# RFMC_DAC.net
KiCad netlist of a schematic drawn in Altium Designer
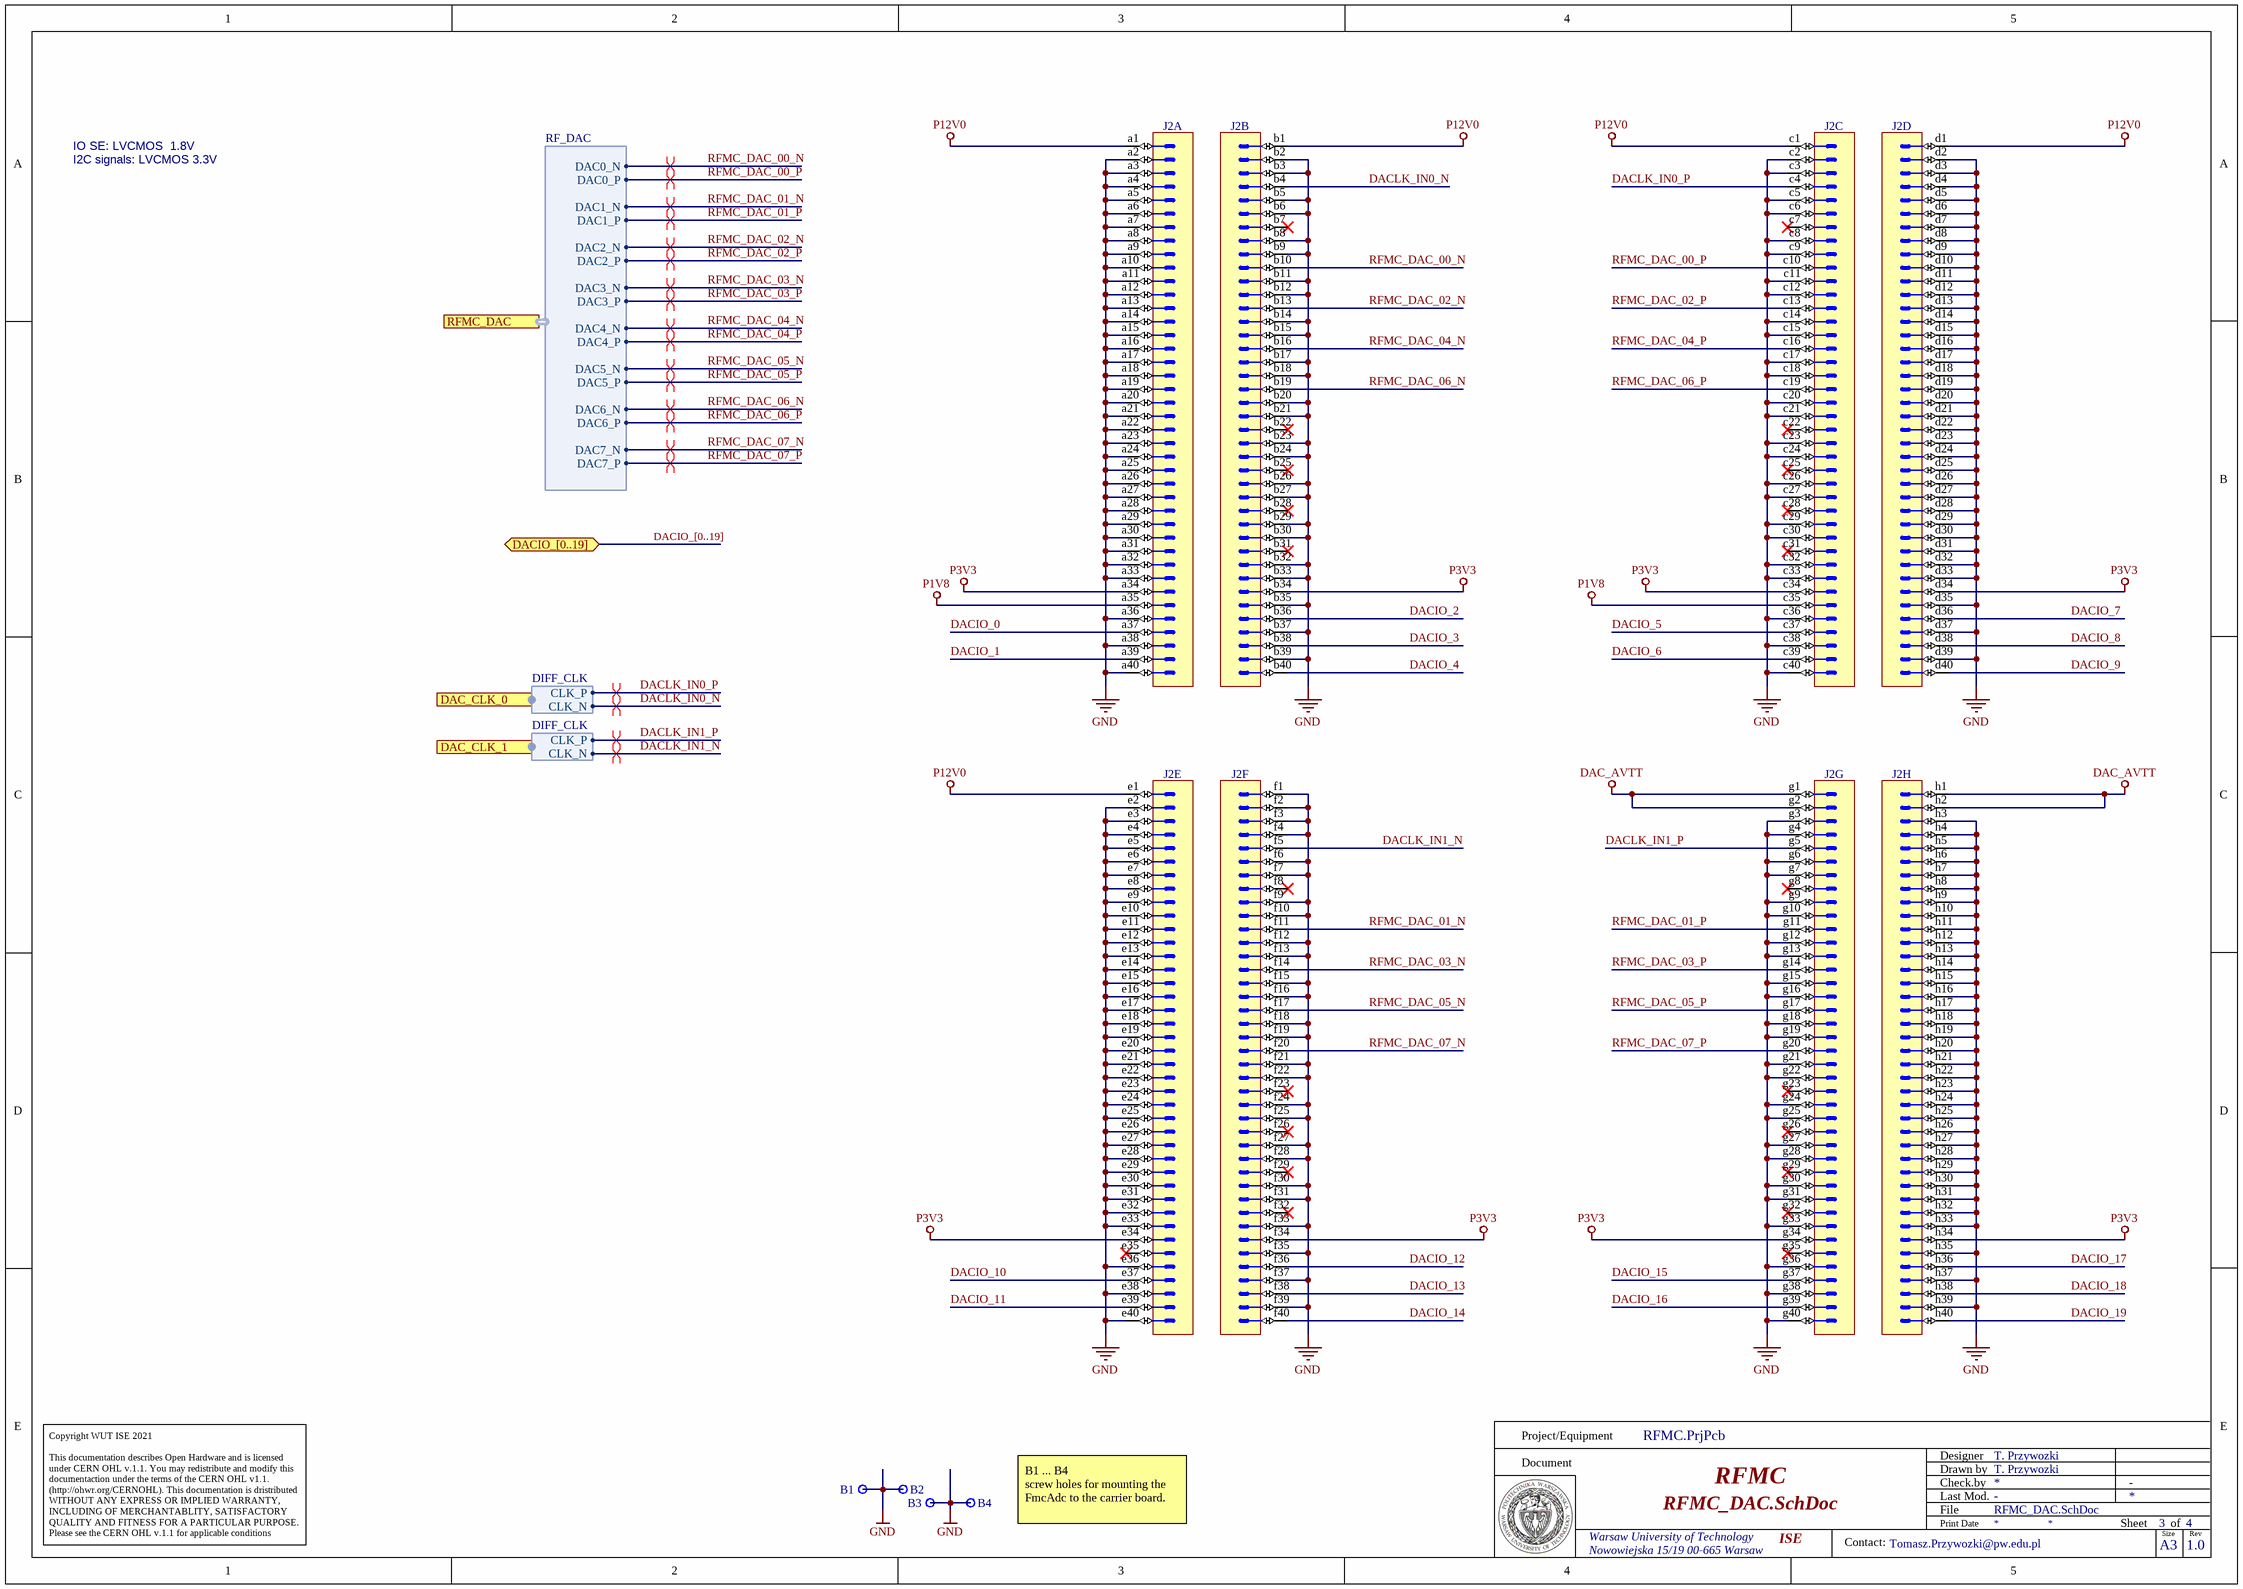
[diagram p0: RFMC_DAC.SchDoc]

(export (version "E")
  (design (tool "Eeschema 10.0.6"))
  (components
    (comp (ref "B1")
      (value "Plated Hole")
      (footprint "MTG270_500")
      (description "Single Terminal Socket")
      (fields (field (name "PART NUMBER") "PLATED_HOLE2.7_PAD5.0") (field (name "AUTHOR") "CERN DEM JMW"))
      (libsource (lib "Eletro-mechanical") (part "Single Terminal Socket"))
    )
    (comp (ref "B2")
      (value "Plated Hole")
      (footprint "MTG270_500")
      (description "Single Terminal Socket")
      (fields (field (name "PART NUMBER") "PLATED_HOLE2.7_PAD5.0") (field (name "AUTHOR") "CERN DEM JMW"))
      (libsource (lib "Eletro-mechanical") (part "Single Terminal Socket"))
    )
    (comp (ref "B3")
      (value "Plated Hole")
      (footprint "MTG270_500")
      (description "Single Terminal Socket")
      (fields (field (name "PART NUMBER") "PLATED_HOLE2.7_PAD5.0") (field (name "AUTHOR") "CERN DEM JMW"))
      (libsource (lib "Eletro-mechanical") (part "Single Terminal Socket"))
    )
    (comp (ref "B4")
      (value "Plated Hole")
      (footprint "MTG270_500")
      (description "Single Terminal Socket")
      (fields (field (name "PART NUMBER") "PLATED_HOLE2.7_PAD5.0") (field (name "AUTHOR") "CERN DEM JMW"))
      (libsource (lib "Eletro-mechanical") (part "Single Terminal Socket"))
    )
    (comp (ref "J2")
      (value "~")
      (footprint "SAMTEC_LPAM-40-01.0-S-08")
      (description "Connector 320 Male contacts in 8 row abcdef")
      (fields
        (field (name "PART NUMBER") "SAMTEC_LPAM-40-01.0-S-08-2-K")
        (field (name "MANUFACTURER") "SAMTEC")
        (field (name "AUTHOR") "CERN DEM BC")
      )
      (libsource (lib "Connectors") (part "Connector 320 Male (8x40) (abcdefgh)"))
    )
  )
  (nets
    (net (code "3") (name "/DACIO_0") (class "Default")
      (node (ref "J2") (pin "a37") (pinfunction "a37_a37") (pintype "bidirectional"))
    )
    (net (code "4") (name "/DACIO_1") (class "Default")
      (node (ref "J2") (pin "a39") (pinfunction "a39_a39") (pintype "bidirectional"))
    )
    (net (code "5") (name "/DACIO_2") (class "Default")
      (node (ref "J2") (pin "b36") (pinfunction "b36_b36") (pintype "bidirectional"))
    )
    (net (code "6") (name "/DACIO_3") (class "Default")
      (node (ref "J2") (pin "b38") (pinfunction "b38_b38") (pintype "bidirectional"))
    )
    (net (code "7") (name "/DACIO_4") (class "Default")
      (node (ref "J2") (pin "b40") (pinfunction "b40_b40") (pintype "bidirectional"))
    )
    (net (code "8") (name "/DACIO_5") (class "Default")
      (node (ref "J2") (pin "c37") (pinfunction "c37_c37") (pintype "bidirectional"))
    )
    (net (code "9") (name "/DACIO_6") (class "Default")
      (node (ref "J2") (pin "c39") (pinfunction "c39_c39") (pintype "bidirectional"))
    )
    (net (code "10") (name "/DACIO_7") (class "Default")
      (node (ref "J2") (pin "d36") (pinfunction "d36_d36") (pintype "bidirectional"))
    )
    (net (code "11") (name "/DACIO_8") (class "Default")
      (node (ref "J2") (pin "d38") (pinfunction "d38_d38") (pintype "bidirectional"))
    )
    (net (code "12") (name "/DACIO_9") (class "Default")
      (node (ref "J2") (pin "d40") (pinfunction "d40_d40") (pintype "bidirectional"))
    )
    (net (code "13") (name "/DACIO_10") (class "Default")
      (node (ref "J2") (pin "e37") (pinfunction "e37_e37") (pintype "bidirectional"))
    )
    (net (code "14") (name "/DACIO_11") (class "Default")
      (node (ref "J2") (pin "e39") (pinfunction "e39_e39") (pintype "bidirectional"))
    )
    (net (code "15") (name "/DACIO_12") (class "Default")
      (node (ref "J2") (pin "f36") (pinfunction "f36_f36") (pintype "bidirectional"))
    )
    (net (code "16") (name "/DACIO_13") (class "Default")
      (node (ref "J2") (pin "f38") (pinfunction "f38_f38") (pintype "bidirectional"))
    )
    (net (code "17") (name "/DACIO_14") (class "Default")
      (node (ref "J2") (pin "f40") (pinfunction "f40_f40") (pintype "bidirectional"))
    )
    (net (code "18") (name "/DACIO_15") (class "Default")
      (node (ref "J2") (pin "g37") (pinfunction "g37_g37") (pintype "bidirectional"))
    )
    (net (code "19") (name "/DACIO_16") (class "Default")
      (node (ref "J2") (pin "g39") (pinfunction "g39_g39") (pintype "bidirectional"))
    )
    (net (code "20") (name "/DACIO_17") (class "Default")
      (node (ref "J2") (pin "h36") (pinfunction "h36_h36") (pintype "bidirectional"))
    )
    (net (code "21") (name "/DACIO_18") (class "Default")
      (node (ref "J2") (pin "h38") (pinfunction "h38_h38") (pintype "bidirectional"))
    )
    (net (code "22") (name "/DACIO_19") (class "Default")
      (node (ref "J2") (pin "h40") (pinfunction "h40_h40") (pintype "bidirectional"))
    )
    (net (code "24") (name "/DACLK_IN0_N") (class "Default")
      (node (ref "J2") (pin "b4") (pinfunction "b4_b4") (pintype "bidirectional"))
    )
    (net (code "25") (name "/DACLK_IN0_P") (class "Default")
      (node (ref "J2") (pin "c4") (pinfunction "c4_c4") (pintype "bidirectional"))
    )
    (net (code "26") (name "/DACLK_IN1_N") (class "Default")
      (node (ref "J2") (pin "f5") (pinfunction "f5_f5") (pintype "bidirectional"))
    )
    (net (code "27") (name "/DACLK_IN1_P") (class "Default")
      (node (ref "J2") (pin "g5") (pinfunction "g5_g5") (pintype "bidirectional"))
    )
    (net (code "28") (name "/RFMC_DAC_00_N") (class "Default")
      (node (ref "J2") (pin "b10") (pinfunction "b10_b10") (pintype "bidirectional"))
    )
    (net (code "29") (name "/RFMC_DAC_00_P") (class "Default")
      (node (ref "J2") (pin "c10") (pinfunction "c10_c10") (pintype "bidirectional"))
    )
    (net (code "30") (name "/RFMC_DAC_01_N") (class "Default")
      (node (ref "J2") (pin "f11") (pinfunction "f11_f11") (pintype "bidirectional"))
    )
    (net (code "31") (name "/RFMC_DAC_01_P") (class "Default")
      (node (ref "J2") (pin "g11") (pinfunction "g11_g11") (pintype "bidirectional"))
    )
    (net (code "32") (name "/RFMC_DAC_02_N") (class "Default")
      (node (ref "J2") (pin "b13") (pinfunction "b13_b13") (pintype "bidirectional"))
    )
    (net (code "33") (name "/RFMC_DAC_02_P") (class "Default")
      (node (ref "J2") (pin "c13") (pinfunction "c13_c13") (pintype "bidirectional"))
    )
    (net (code "34") (name "/RFMC_DAC_03_N") (class "Default")
      (node (ref "J2") (pin "f14") (pinfunction "f14_f14") (pintype "bidirectional"))
    )
    (net (code "35") (name "/RFMC_DAC_03_P") (class "Default")
      (node (ref "J2") (pin "g14") (pinfunction "g14_g14") (pintype "bidirectional"))
    )
    (net (code "36") (name "/RFMC_DAC_04_N") (class "Default")
      (node (ref "J2") (pin "b16") (pinfunction "b16_b16") (pintype "bidirectional"))
    )
    (net (code "37") (name "/RFMC_DAC_04_P") (class "Default")
      (node (ref "J2") (pin "c16") (pinfunction "c16_c16") (pintype "bidirectional"))
    )
    (net (code "38") (name "/RFMC_DAC_05_N") (class "Default")
      (node (ref "J2") (pin "f17") (pinfunction "f17_f17") (pintype "bidirectional"))
    )
    (net (code "39") (name "/RFMC_DAC_05_P") (class "Default")
      (node (ref "J2") (pin "g17") (pinfunction "g17_g17") (pintype "bidirectional"))
    )
    (net (code "40") (name "/RFMC_DAC_06_N") (class "Default")
      (node (ref "J2") (pin "b19") (pinfunction "b19_b19") (pintype "bidirectional"))
    )
    (net (code "41") (name "/RFMC_DAC_06_P") (class "Default")
      (node (ref "J2") (pin "c19") (pinfunction "c19_c19") (pintype "bidirectional"))
    )
    (net (code "42") (name "/RFMC_DAC_07_N") (class "Default")
      (node (ref "J2") (pin "f20") (pinfunction "f20_f20") (pintype "bidirectional"))
    )
    (net (code "43") (name "/RFMC_DAC_07_P") (class "Default")
      (node (ref "J2") (pin "g20") (pinfunction "g20_g20") (pintype "bidirectional"))
    )
    (net (code "46") (name "DAC_AVTT") (class "Default")
      (node (ref "J2") (pin "g1") (pinfunction "g1_g1") (pintype "bidirectional"))
      (node (ref "J2") (pin "g2") (pinfunction "g2_g2") (pintype "bidirectional"))
      (node (ref "J2") (pin "h1") (pinfunction "h1_h1") (pintype "bidirectional"))
      (node (ref "J2") (pin "h2") (pinfunction "h2_h2") (pintype "bidirectional"))
    )
    (net (code "47") (name "GND") (class "Default")
      (node (ref "B1") (pin "1") (pinfunction "1_1") (pintype "bidirectional"))
      (node (ref "B2") (pin "1") (pinfunction "1_1") (pintype "bidirectional"))
      (node (ref "B3") (pin "1") (pinfunction "1_1") (pintype "bidirectional"))
      (node (ref "B4") (pin "1") (pinfunction "1_1") (pintype "bidirectional"))
      (node (ref "J2") (pin "a10") (pinfunction "a10_a10") (pintype "bidirectional"))
      (node (ref "J2") (pin "a11") (pinfunction "a11_a11") (pintype "bidirectional"))
      (node (ref "J2") (pin "a12") (pinfunction "a12_a12") (pintype "bidirectional"))
      (node (ref "J2") (pin "a13") (pinfunction "a13_a13") (pintype "bidirectional"))
      (node (ref "J2") (pin "a14") (pinfunction "a14_a14") (pintype "bidirectional"))
      (node (ref "J2") (pin "a15") (pinfunction "a15_a15") (pintype "bidirectional"))
      (node (ref "J2") (pin "a16") (pinfunction "a16_a16") (pintype "bidirectional"))
      (node (ref "J2") (pin "a17") (pinfunction "a17_a17") (pintype "bidirectional"))
      (node (ref "J2") (pin "a18") (pinfunction "a18_a18") (pintype "bidirectional"))
      (node (ref "J2") (pin "a19") (pinfunction "a19_a19") (pintype "bidirectional"))
      (node (ref "J2") (pin "a2") (pinfunction "a2_a2") (pintype "bidirectional"))
      (node (ref "J2") (pin "a20") (pinfunction "a20_a20") (pintype "bidirectional"))
      (node (ref "J2") (pin "a21") (pinfunction "a21_a21") (pintype "bidirectional"))
      (node (ref "J2") (pin "a22") (pinfunction "a22_a22") (pintype "bidirectional"))
      (node (ref "J2") (pin "a23") (pinfunction "a23_a23") (pintype "bidirectional"))
      (node (ref "J2") (pin "a24") (pinfunction "a24_a24") (pintype "bidirectional"))
      (node (ref "J2") (pin "a25") (pinfunction "a25_a25") (pintype "bidirectional"))
      (node (ref "J2") (pin "a26") (pinfunction "a26_a26") (pintype "bidirectional"))
      (node (ref "J2") (pin "a27") (pinfunction "a27_a27") (pintype "bidirectional"))
      (node (ref "J2") (pin "a28") (pinfunction "a28_a28") (pintype "bidirectional"))
      (node (ref "J2") (pin "a29") (pinfunction "a29_a29") (pintype "bidirectional"))
      (node (ref "J2") (pin "a3") (pinfunction "a3_a3") (pintype "bidirectional"))
      (node (ref "J2") (pin "a30") (pinfunction "a30_a30") (pintype "bidirectional"))
      (node (ref "J2") (pin "a31") (pinfunction "a31_a31") (pintype "bidirectional"))
      (node (ref "J2") (pin "a32") (pinfunction "a32_a32") (pintype "bidirectional"))
      (node (ref "J2") (pin "a33") (pinfunction "a33_a33") (pintype "bidirectional"))
      (node (ref "J2") (pin "a36") (pinfunction "a36_a36") (pintype "bidirectional"))
      (node (ref "J2") (pin "a38") (pinfunction "a38_a38") (pintype "bidirectional"))
      (node (ref "J2") (pin "a4") (pinfunction "a4_a4") (pintype "bidirectional"))
      (node (ref "J2") (pin "a40") (pinfunction "a40_a40") (pintype "bidirectional"))
      (node (ref "J2") (pin "a5") (pinfunction "a5_a5") (pintype "bidirectional"))
      (node (ref "J2") (pin "a6") (pinfunction "a6_a6") (pintype "bidirectional"))
      (node (ref "J2") (pin "a7") (pinfunction "a7_a7") (pintype "bidirectional"))
      (node (ref "J2") (pin "a8") (pinfunction "a8_a8") (pintype "bidirectional"))
      (node (ref "J2") (pin "a9") (pinfunction "a9_a9") (pintype "bidirectional"))
      (node (ref "J2") (pin "b11") (pinfunction "b11_b11") (pintype "bidirectional"))
      (node (ref "J2") (pin "b12") (pinfunction "b12_b12") (pintype "bidirectional"))
      (node (ref "J2") (pin "b14") (pinfunction "b14_b14") (pintype "bidirectional"))
      (node (ref "J2") (pin "b15") (pinfunction "b15_b15") (pintype "bidirectional"))
      (node (ref "J2") (pin "b17") (pinfunction "b17_b17") (pintype "bidirectional"))
      (node (ref "J2") (pin "b18") (pinfunction "b18_b18") (pintype "bidirectional"))
      (node (ref "J2") (pin "b2") (pinfunction "b2_b2") (pintype "bidirectional"))
      (node (ref "J2") (pin "b20") (pinfunction "b20_b20") (pintype "bidirectional"))
      (node (ref "J2") (pin "b21") (pinfunction "b21_b21") (pintype "bidirectional"))
      (node (ref "J2") (pin "b23") (pinfunction "b23_b23") (pintype "bidirectional"))
      (node (ref "J2") (pin "b24") (pinfunction "b24_b24") (pintype "bidirectional"))
      (node (ref "J2") (pin "b26") (pinfunction "b26_b26") (pintype "bidirectional"))
      (node (ref "J2") (pin "b27") (pinfunction "b27_b27") (pintype "bidirectional"))
      (node (ref "J2") (pin "b29") (pinfunction "b29_b29") (pintype "bidirectional"))
      (node (ref "J2") (pin "b3") (pinfunction "b3_b3") (pintype "bidirectional"))
      (node (ref "J2") (pin "b30") (pinfunction "b30_b30") (pintype "bidirectional"))
      (node (ref "J2") (pin "b32") (pinfunction "b32_b32") (pintype "bidirectional"))
      (node (ref "J2") (pin "b33") (pinfunction "b33_b33") (pintype "bidirectional"))
      (node (ref "J2") (pin "b35") (pinfunction "b35_b35") (pintype "bidirectional"))
      (node (ref "J2") (pin "b37") (pinfunction "b37_b37") (pintype "bidirectional"))
      (node (ref "J2") (pin "b39") (pinfunction "b39_b39") (pintype "bidirectional"))
      (node (ref "J2") (pin "b5") (pinfunction "b5_b5") (pintype "bidirectional"))
      (node (ref "J2") (pin "b6") (pinfunction "b6_b6") (pintype "bidirectional"))
      (node (ref "J2") (pin "b8") (pinfunction "b8_b8") (pintype "bidirectional"))
      (node (ref "J2") (pin "b9") (pinfunction "b9_b9") (pintype "bidirectional"))
      (node (ref "J2") (pin "c11") (pinfunction "c11_c11") (pintype "bidirectional"))
      (node (ref "J2") (pin "c12") (pinfunction "c12_c12") (pintype "bidirectional"))
      (node (ref "J2") (pin "c14") (pinfunction "c14_c14") (pintype "bidirectional"))
      (node (ref "J2") (pin "c15") (pinfunction "c15_c15") (pintype "bidirectional"))
      (node (ref "J2") (pin "c17") (pinfunction "c17_c17") (pintype "bidirectional"))
      (node (ref "J2") (pin "c18") (pinfunction "c18_c18") (pintype "bidirectional"))
      (node (ref "J2") (pin "c2") (pinfunction "c2_c2") (pintype "bidirectional"))
      (node (ref "J2") (pin "c20") (pinfunction "c20_c20") (pintype "bidirectional"))
      (node (ref "J2") (pin "c21") (pinfunction "c21_c21") (pintype "bidirectional"))
      (node (ref "J2") (pin "c23") (pinfunction "c23_c23") (pintype "bidirectional"))
      (node (ref "J2") (pin "c24") (pinfunction "c24_c24") (pintype "bidirectional"))
      (node (ref "J2") (pin "c26") (pinfunction "c26_c26") (pintype "bidirectional"))
      (node (ref "J2") (pin "c27") (pinfunction "c27_c27") (pintype "bidirectional"))
      (node (ref "J2") (pin "c29") (pinfunction "c29_c29") (pintype "bidirectional"))
      (node (ref "J2") (pin "c3") (pinfunction "c3_c3") (pintype "bidirectional"))
      (node (ref "J2") (pin "c30") (pinfunction "c30_c30") (pintype "bidirectional"))
      (node (ref "J2") (pin "c32") (pinfunction "c32_c32") (pintype "bidirectional"))
      (node (ref "J2") (pin "c33") (pinfunction "c33_c33") (pintype "bidirectional"))
      (node (ref "J2") (pin "c36") (pinfunction "c36_c36") (pintype "bidirectional"))
      (node (ref "J2") (pin "c38") (pinfunction "c38_c38") (pintype "bidirectional"))
      (node (ref "J2") (pin "c40") (pinfunction "c40_c40") (pintype "bidirectional"))
      (node (ref "J2") (pin "c5") (pinfunction "c5_c5") (pintype "bidirectional"))
      (node (ref "J2") (pin "c6") (pinfunction "c6_c6") (pintype "bidirectional"))
      (node (ref "J2") (pin "c8") (pinfunction "c8_c8") (pintype "bidirectional"))
      (node (ref "J2") (pin "c9") (pinfunction "c9_c9") (pintype "bidirectional"))
      (node (ref "J2") (pin "d10") (pinfunction "d10_d10") (pintype "bidirectional"))
      (node (ref "J2") (pin "d11") (pinfunction "d11_d11") (pintype "bidirectional"))
      (node (ref "J2") (pin "d12") (pinfunction "d12_d12") (pintype "bidirectional"))
      (node (ref "J2") (pin "d13") (pinfunction "d13_d13") (pintype "bidirectional"))
      (node (ref "J2") (pin "d14") (pinfunction "d14_d14") (pintype "bidirectional"))
      (node (ref "J2") (pin "d15") (pinfunction "d15_d15") (pintype "bidirectional"))
      (node (ref "J2") (pin "d16") (pinfunction "d16_d16") (pintype "bidirectional"))
      (node (ref "J2") (pin "d17") (pinfunction "d17_d17") (pintype "bidirectional"))
      (node (ref "J2") (pin "d18") (pinfunction "d18_d18") (pintype "bidirectional"))
      (node (ref "J2") (pin "d19") (pinfunction "d19_d19") (pintype "bidirectional"))
      (node (ref "J2") (pin "d2") (pinfunction "d2_d2") (pintype "bidirectional"))
      (node (ref "J2") (pin "d20") (pinfunction "d20_d20") (pintype "bidirectional"))
      (node (ref "J2") (pin "d21") (pinfunction "d21_d21") (pintype "bidirectional"))
      (node (ref "J2") (pin "d22") (pinfunction "d22_d22") (pintype "bidirectional"))
      (node (ref "J2") (pin "d23") (pinfunction "d23_d23") (pintype "bidirectional"))
      (node (ref "J2") (pin "d24") (pinfunction "d24_d24") (pintype "bidirectional"))
      (node (ref "J2") (pin "d25") (pinfunction "d25_d25") (pintype "bidirectional"))
      (node (ref "J2") (pin "d26") (pinfunction "d26_d26") (pintype "bidirectional"))
      (node (ref "J2") (pin "d27") (pinfunction "d27_d27") (pintype "bidirectional"))
      (node (ref "J2") (pin "d28") (pinfunction "d28_d28") (pintype "bidirectional"))
      (node (ref "J2") (pin "d29") (pinfunction "d29_d29") (pintype "bidirectional"))
      (node (ref "J2") (pin "d3") (pinfunction "d3_d3") (pintype "bidirectional"))
      (node (ref "J2") (pin "d30") (pinfunction "d30_d30") (pintype "bidirectional"))
      (node (ref "J2") (pin "d31") (pinfunction "d31_d31") (pintype "bidirectional"))
      (node (ref "J2") (pin "d32") (pinfunction "d32_d32") (pintype "bidirectional"))
      (node (ref "J2") (pin "d33") (pinfunction "d33_d33") (pintype "bidirectional"))
      (node (ref "J2") (pin "d35") (pinfunction "d35_d35") (pintype "bidirectional"))
      (node (ref "J2") (pin "d37") (pinfunction "d37_d37") (pintype "bidirectional"))
      (node (ref "J2") (pin "d39") (pinfunction "d39_d39") (pintype "bidirectional"))
      (node (ref "J2") (pin "d4") (pinfunction "d4_d4") (pintype "bidirectional"))
      (node (ref "J2") (pin "d5") (pinfunction "d5_d5") (pintype "bidirectional"))
      (node (ref "J2") (pin "d6") (pinfunction "d6_d6") (pintype "bidirectional"))
      (node (ref "J2") (pin "d7") (pinfunction "d7_d7") (pintype "bidirectional"))
      (node (ref "J2") (pin "d8") (pinfunction "d8_d8") (pintype "bidirectional"))
      (node (ref "J2") (pin "d9") (pinfunction "d9_d9") (pintype "bidirectional"))
      (node (ref "J2") (pin "e10") (pinfunction "e10_e10") (pintype "bidirectional"))
      (node (ref "J2") (pin "e11") (pinfunction "e11_e11") (pintype "bidirectional"))
      (node (ref "J2") (pin "e12") (pinfunction "e12_e12") (pintype "bidirectional"))
      (node (ref "J2") (pin "e13") (pinfunction "e13_e13") (pintype "bidirectional"))
      (node (ref "J2") (pin "e14") (pinfunction "e14_e14") (pintype "bidirectional"))
      (node (ref "J2") (pin "e15") (pinfunction "e15_e15") (pintype "bidirectional"))
      (node (ref "J2") (pin "e16") (pinfunction "e16_e16") (pintype "bidirectional"))
      (node (ref "J2") (pin "e17") (pinfunction "e17_e17") (pintype "bidirectional"))
      (node (ref "J2") (pin "e18") (pinfunction "e18_e18") (pintype "bidirectional"))
      (node (ref "J2") (pin "e19") (pinfunction "e19_e19") (pintype "bidirectional"))
      (node (ref "J2") (pin "e2") (pinfunction "e2_e2") (pintype "bidirectional"))
      (node (ref "J2") (pin "e20") (pinfunction "e20_e20") (pintype "bidirectional"))
      (node (ref "J2") (pin "e21") (pinfunction "e21_e21") (pintype "bidirectional"))
      (node (ref "J2") (pin "e22") (pinfunction "e22_e22") (pintype "bidirectional"))
      (node (ref "J2") (pin "e23") (pinfunction "e23_e23") (pintype "bidirectional"))
      (node (ref "J2") (pin "e24") (pinfunction "e24_e24") (pintype "bidirectional"))
      (node (ref "J2") (pin "e25") (pinfunction "e25_e25") (pintype "bidirectional"))
      (node (ref "J2") (pin "e26") (pinfunction "e26_e26") (pintype "bidirectional"))
      (node (ref "J2") (pin "e27") (pinfunction "e27_e27") (pintype "bidirectional"))
      (node (ref "J2") (pin "e28") (pinfunction "e28_e28") (pintype "bidirectional"))
      (node (ref "J2") (pin "e29") (pinfunction "e29_e29") (pintype "bidirectional"))
      (node (ref "J2") (pin "e3") (pinfunction "e3_e3") (pintype "bidirectional"))
      (node (ref "J2") (pin "e30") (pinfunction "e30_e30") (pintype "bidirectional"))
      (node (ref "J2") (pin "e31") (pinfunction "e31_e31") (pintype "bidirectional"))
      (node (ref "J2") (pin "e32") (pinfunction "e32_e32") (pintype "bidirectional"))
      (node (ref "J2") (pin "e33") (pinfunction "e33_e33") (pintype "bidirectional"))
      (node (ref "J2") (pin "e36") (pinfunction "e36_e36") (pintype "bidirectional"))
      (node (ref "J2") (pin "e38") (pinfunction "e38_e38") (pintype "bidirectional"))
      (node (ref "J2") (pin "e4") (pinfunction "e4_e4") (pintype "bidirectional"))
      (node (ref "J2") (pin "e40") (pinfunction "e40_e40") (pintype "bidirectional"))
      (node (ref "J2") (pin "e5") (pinfunction "e5_e5") (pintype "bidirectional"))
      (node (ref "J2") (pin "e6") (pinfunction "e6_e6") (pintype "bidirectional"))
      (node (ref "J2") (pin "e7") (pinfunction "e7_e7") (pintype "bidirectional"))
      (node (ref "J2") (pin "e8") (pinfunction "e8_e8") (pintype "bidirectional"))
      (node (ref "J2") (pin "e9") (pinfunction "e9_e9") (pintype "bidirectional"))
      (node (ref "J2") (pin "f1") (pinfunction "f1_f1") (pintype "bidirectional"))
      (node (ref "J2") (pin "f10") (pinfunction "f10_f10") (pintype "bidirectional"))
      (node (ref "J2") (pin "f12") (pinfunction "f12_f12") (pintype "bidirectional"))
      (node (ref "J2") (pin "f13") (pinfunction "f13_f13") (pintype "bidirectional"))
      (node (ref "J2") (pin "f15") (pinfunction "f15_f15") (pintype "bidirectional"))
      (node (ref "J2") (pin "f16") (pinfunction "f16_f16") (pintype "bidirectional"))
      (node (ref "J2") (pin "f18") (pinfunction "f18_f18") (pintype "bidirectional"))
      (node (ref "J2") (pin "f19") (pinfunction "f19_f19") (pintype "bidirectional"))
      (node (ref "J2") (pin "f2") (pinfunction "f2_f2") (pintype "bidirectional"))
      (node (ref "J2") (pin "f21") (pinfunction "f21_f21") (pintype "bidirectional"))
      (node (ref "J2") (pin "f22") (pinfunction "f22_f22") (pintype "bidirectional"))
      (node (ref "J2") (pin "f24") (pinfunction "f24_f24") (pintype "bidirectional"))
      (node (ref "J2") (pin "f25") (pinfunction "f25_f25") (pintype "bidirectional"))
      (node (ref "J2") (pin "f27") (pinfunction "f27_f27") (pintype "bidirectional"))
      (node (ref "J2") (pin "f28") (pinfunction "f28_f28") (pintype "bidirectional"))
      (node (ref "J2") (pin "f3") (pinfunction "f3_f3") (pintype "bidirectional"))
      (node (ref "J2") (pin "f30") (pinfunction "f30_f30") (pintype "bidirectional"))
      (node (ref "J2") (pin "f31") (pinfunction "f31_f31") (pintype "bidirectional"))
      (node (ref "J2") (pin "f33") (pinfunction "f33_f33") (pintype "bidirectional"))
      (node (ref "J2") (pin "f35") (pinfunction "f35_f35") (pintype "bidirectional"))
      (node (ref "J2") (pin "f37") (pinfunction "f37_f37") (pintype "bidirectional"))
      (node (ref "J2") (pin "f39") (pinfunction "f39_f39") (pintype "bidirectional"))
      (node (ref "J2") (pin "f4") (pinfunction "f4_f4") (pintype "bidirectional"))
      (node (ref "J2") (pin "f6") (pinfunction "f6_f6") (pintype "bidirectional"))
      (node (ref "J2") (pin "f7") (pinfunction "f7_f7") (pintype "bidirectional"))
      (node (ref "J2") (pin "f9") (pinfunction "f9_f9") (pintype "bidirectional"))
      (node (ref "J2") (pin "g10") (pinfunction "g10_g10") (pintype "bidirectional"))
      (node (ref "J2") (pin "g12") (pinfunction "g12_g12") (pintype "bidirectional"))
      (node (ref "J2") (pin "g13") (pinfunction "g13_g13") (pintype "bidirectional"))
      (node (ref "J2") (pin "g15") (pinfunction "g15_g15") (pintype "bidirectional"))
      (node (ref "J2") (pin "g16") (pinfunction "g16_g16") (pintype "bidirectional"))
      (node (ref "J2") (pin "g18") (pinfunction "g18_g18") (pintype "bidirectional"))
      (node (ref "J2") (pin "g19") (pinfunction "g19_g19") (pintype "bidirectional"))
      (node (ref "J2") (pin "g21") (pinfunction "g21_g21") (pintype "bidirectional"))
      (node (ref "J2") (pin "g22") (pinfunction "g22_g22") (pintype "bidirectional"))
      (node (ref "J2") (pin "g24") (pinfunction "g24_g24") (pintype "bidirectional"))
      (node (ref "J2") (pin "g25") (pinfunction "g25_g25") (pintype "bidirectional"))
      (node (ref "J2") (pin "g27") (pinfunction "g27_g27") (pintype "bidirectional"))
      (node (ref "J2") (pin "g28") (pinfunction "g28_g28") (pintype "bidirectional"))
      (node (ref "J2") (pin "g3") (pinfunction "g3_g3") (pintype "bidirectional"))
      (node (ref "J2") (pin "g30") (pinfunction "g30_g30") (pintype "bidirectional"))
      (node (ref "J2") (pin "g31") (pinfunction "g31_g31") (pintype "bidirectional"))
      (node (ref "J2") (pin "g33") (pinfunction "g33_g33") (pintype "bidirectional"))
      (node (ref "J2") (pin "g36") (pinfunction "g36_g36") (pintype "bidirectional"))
      (node (ref "J2") (pin "g38") (pinfunction "g38_g38") (pintype "bidirectional"))
      (node (ref "J2") (pin "g4") (pinfunction "g4_g4") (pintype "bidirectional"))
      (node (ref "J2") (pin "g40") (pinfunction "g40_g40") (pintype "bidirectional"))
      (node (ref "J2") (pin "g6") (pinfunction "g6_g6") (pintype "bidirectional"))
      (node (ref "J2") (pin "g7") (pinfunction "g7_g7") (pintype "bidirectional"))
      (node (ref "J2") (pin "g9") (pinfunction "g9_g9") (pintype "bidirectional"))
      (node (ref "J2") (pin "h10") (pinfunction "h10_h10") (pintype "bidirectional"))
      (node (ref "J2") (pin "h11") (pinfunction "h11_h11") (pintype "bidirectional"))
      (node (ref "J2") (pin "h12") (pinfunction "h12_h12") (pintype "bidirectional"))
      (node (ref "J2") (pin "h13") (pinfunction "h13_h13") (pintype "bidirectional"))
      (node (ref "J2") (pin "h14") (pinfunction "h14_h14") (pintype "bidirectional"))
      (node (ref "J2") (pin "h15") (pinfunction "h15_h15") (pintype "bidirectional"))
      (node (ref "J2") (pin "h16") (pinfunction "h16_h16") (pintype "bidirectional"))
      (node (ref "J2") (pin "h17") (pinfunction "h17_h17") (pintype "bidirectional"))
      (node (ref "J2") (pin "h18") (pinfunction "h18_h18") (pintype "bidirectional"))
      (node (ref "J2") (pin "h19") (pinfunction "h19_h19") (pintype "bidirectional"))
      (node (ref "J2") (pin "h20") (pinfunction "h20_h20") (pintype "bidirectional"))
      (node (ref "J2") (pin "h21") (pinfunction "h21_h21") (pintype "bidirectional"))
      (node (ref "J2") (pin "h22") (pinfunction "h22_h22") (pintype "bidirectional"))
      (node (ref "J2") (pin "h23") (pinfunction "h23_h23") (pintype "bidirectional"))
      (node (ref "J2") (pin "h24") (pinfunction "h24_h24") (pintype "bidirectional"))
      (node (ref "J2") (pin "h25") (pinfunction "h25_h25") (pintype "bidirectional"))
      (node (ref "J2") (pin "h26") (pinfunction "h26_h26") (pintype "bidirectional"))
      (node (ref "J2") (pin "h27") (pinfunction "h27_h27") (pintype "bidirectional"))
      (node (ref "J2") (pin "h28") (pinfunction "h28_h28") (pintype "bidirectional"))
      (node (ref "J2") (pin "h29") (pinfunction "h29_h29") (pintype "bidirectional"))
      (node (ref "J2") (pin "h3") (pinfunction "h3_h3") (pintype "bidirectional"))
      (node (ref "J2") (pin "h30") (pinfunction "h30_h30") (pintype "bidirectional"))
      (node (ref "J2") (pin "h31") (pinfunction "h31_h31") (pintype "bidirectional"))
      (node (ref "J2") (pin "h32") (pinfunction "h32_h32") (pintype "bidirectional"))
      (node (ref "J2") (pin "h33") (pinfunction "h33_h33") (pintype "bidirectional"))
      (node (ref "J2") (pin "h35") (pinfunction "h35_h35") (pintype "bidirectional"))
      (node (ref "J2") (pin "h37") (pinfunction "h37_h37") (pintype "bidirectional"))
      (node (ref "J2") (pin "h39") (pinfunction "h39_h39") (pintype "bidirectional"))
      (node (ref "J2") (pin "h4") (pinfunction "h4_h4") (pintype "bidirectional"))
      (node (ref "J2") (pin "h5") (pinfunction "h5_h5") (pintype "bidirectional"))
      (node (ref "J2") (pin "h6") (pinfunction "h6_h6") (pintype "bidirectional"))
      (node (ref "J2") (pin "h7") (pinfunction "h7_h7") (pintype "bidirectional"))
      (node (ref "J2") (pin "h8") (pinfunction "h8_h8") (pintype "bidirectional"))
      (node (ref "J2") (pin "h9") (pinfunction "h9_h9") (pintype "bidirectional"))
    )
    (net (code "48") (name "P1V8") (class "Default")
      (node (ref "J2") (pin "a35") (pinfunction "a35_a35") (pintype "bidirectional"))
      (node (ref "J2") (pin "c35") (pinfunction "c35_c35") (pintype "bidirectional"))
    )
    (net (code "49") (name "P3V3") (class "Default")
      (node (ref "J2") (pin "a34") (pinfunction "a34_a34") (pintype "bidirectional"))
      (node (ref "J2") (pin "b34") (pinfunction "b34_b34") (pintype "bidirectional"))
      (node (ref "J2") (pin "c34") (pinfunction "c34_c34") (pintype "bidirectional"))
      (node (ref "J2") (pin "d34") (pinfunction "d34_d34") (pintype "bidirectional"))
      (node (ref "J2") (pin "e34") (pinfunction "e34_e34") (pintype "bidirectional"))
      (node (ref "J2") (pin "f34") (pinfunction "f34_f34") (pintype "bidirectional"))
      (node (ref "J2") (pin "g34") (pinfunction "g34_g34") (pintype "bidirectional"))
      (node (ref "J2") (pin "h34") (pinfunction "h34_h34") (pintype "bidirectional"))
    )
    (net (code "50") (name "P12V0") (class "Default")
      (node (ref "J2") (pin "a1") (pinfunction "a1_a1") (pintype "bidirectional"))
      (node (ref "J2") (pin "b1") (pinfunction "b1_b1") (pintype "bidirectional"))
      (node (ref "J2") (pin "c1") (pinfunction "c1_c1") (pintype "bidirectional"))
      (node (ref "J2") (pin "d1") (pinfunction "d1_d1") (pintype "bidirectional"))
      (node (ref "J2") (pin "e1") (pinfunction "e1_e1") (pintype "bidirectional"))
    )
    (net (code "51") (name "unconnected-(J2-Padb7)") (class "Default")
      (node (ref "J2") (pin "b7") (pinfunction "b7_b7") (pintype "bidirectional+no_connect"))
    )
    (net (code "52") (name "unconnected-(J2-Padb22)") (class "Default")
      (node (ref "J2") (pin "b22") (pinfunction "b22_b22") (pintype "bidirectional+no_connect"))
    )
    (net (code "53") (name "unconnected-(J2-Padb25)") (class "Default")
      (node (ref "J2") (pin "b25") (pinfunction "b25_b25") (pintype "bidirectional+no_connect"))
    )
    (net (code "54") (name "unconnected-(J2-Padb28)") (class "Default")
      (node (ref "J2") (pin "b28") (pinfunction "b28_b28") (pintype "bidirectional+no_connect"))
    )
    (net (code "55") (name "unconnected-(J2-Padb31)") (class "Default")
      (node (ref "J2") (pin "b31") (pinfunction "b31_b31") (pintype "bidirectional+no_connect"))
    )
    (net (code "56") (name "unconnected-(J2-Padc7)") (class "Default")
      (node (ref "J2") (pin "c7") (pinfunction "c7_c7") (pintype "bidirectional+no_connect"))
    )
    (net (code "57") (name "unconnected-(J2-Padc22)") (class "Default")
      (node (ref "J2") (pin "c22") (pinfunction "c22_c22") (pintype "bidirectional+no_connect"))
    )
    (net (code "58") (name "unconnected-(J2-Padc25)") (class "Default")
      (node (ref "J2") (pin "c25") (pinfunction "c25_c25") (pintype "bidirectional+no_connect"))
    )
    (net (code "59") (name "unconnected-(J2-Padc28)") (class "Default")
      (node (ref "J2") (pin "c28") (pinfunction "c28_c28") (pintype "bidirectional+no_connect"))
    )
    (net (code "60") (name "unconnected-(J2-Padc31)") (class "Default")
      (node (ref "J2") (pin "c31") (pinfunction "c31_c31") (pintype "bidirectional+no_connect"))
    )
    (net (code "61") (name "unconnected-(J2-Pade35)") (class "Default")
      (node (ref "J2") (pin "e35") (pinfunction "e35_e35") (pintype "bidirectional+no_connect"))
    )
    (net (code "62") (name "unconnected-(J2-Padf8)") (class "Default")
      (node (ref "J2") (pin "f8") (pinfunction "f8_f8") (pintype "bidirectional+no_connect"))
    )
    (net (code "63") (name "unconnected-(J2-Padf23)") (class "Default")
      (node (ref "J2") (pin "f23") (pinfunction "f23_f23") (pintype "bidirectional+no_connect"))
    )
    (net (code "64") (name "unconnected-(J2-Padf26)") (class "Default")
      (node (ref "J2") (pin "f26") (pinfunction "f26_f26") (pintype "bidirectional+no_connect"))
    )
    (net (code "65") (name "unconnected-(J2-Padf29)") (class "Default")
      (node (ref "J2") (pin "f29") (pinfunction "f29_f29") (pintype "bidirectional+no_connect"))
    )
    (net (code "66") (name "unconnected-(J2-Padf32)") (class "Default")
      (node (ref "J2") (pin "f32") (pinfunction "f32_f32") (pintype "bidirectional+no_connect"))
    )
    (net (code "67") (name "unconnected-(J2-Padg8)") (class "Default")
      (node (ref "J2") (pin "g8") (pinfunction "g8_g8") (pintype "bidirectional+no_connect"))
    )
    (net (code "68") (name "unconnected-(J2-Padg23)") (class "Default")
      (node (ref "J2") (pin "g23") (pinfunction "g23_g23") (pintype "bidirectional+no_connect"))
    )
    (net (code "69") (name "unconnected-(J2-Padg26)") (class "Default")
      (node (ref "J2") (pin "g26") (pinfunction "g26_g26") (pintype "bidirectional+no_connect"))
    )
    (net (code "70") (name "unconnected-(J2-Padg29)") (class "Default")
      (node (ref "J2") (pin "g29") (pinfunction "g29_g29") (pintype "bidirectional+no_connect"))
    )
    (net (code "71") (name "unconnected-(J2-Padg32)") (class "Default")
      (node (ref "J2") (pin "g32") (pinfunction "g32_g32") (pintype "bidirectional+no_connect"))
    )
    (net (code "72") (name "unconnected-(J2-Padg35)") (class "Default")
      (node (ref "J2") (pin "g35") (pinfunction "g35_g35") (pintype "bidirectional+no_connect"))
    )
  )
)
